# shutdown_circuit.net
KiCad netlist of a schematic drawn in Altium Designer
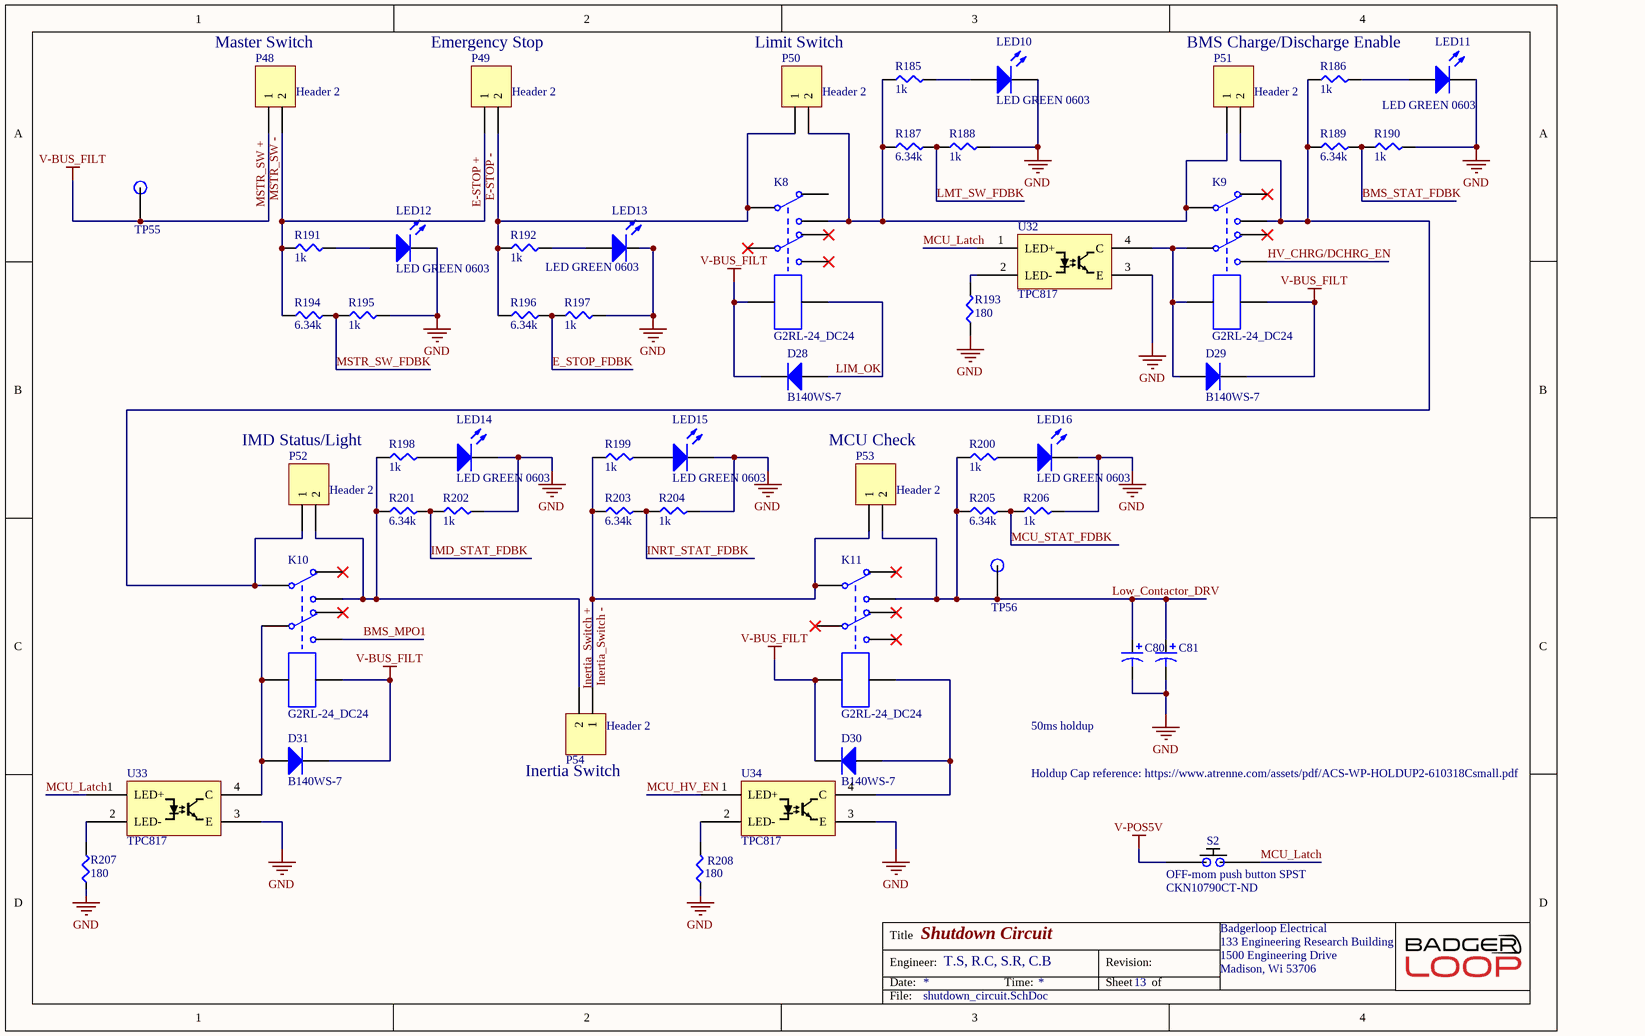
[diagram p0: shutdown_circuit.SchDoc]

(export (version "E")
  (design (tool "Eeschema 10.0.6"))
  (components
    (comp (ref "C80")
      (value "PCR1J101MCL1GS")
      (footprint "CAPAE110103X126M")
      (description "CAP ALUM POLY 100UF 20% 63V SMD")
      (fields (field (name "MANUFACTURER") "Nichicon") (field (name "TOLERANCE") "20%"))
      (libsource (lib "capacitors") (part "PCR1J101MCL1GS"))
    )
    (comp (ref "C81")
      (value "PCR1J101MCL1GS")
      (footprint "CAPAE110103X126M")
      (description "CAP ALUM POLY 100UF 20% 63V SMD")
      (fields (field (name "MANUFACTURER") "Nichicon") (field (name "TOLERANCE") "20%"))
      (libsource (lib "capacitors") (part "PCR1J101MCL1GS"))
    )
    (comp (ref "D28")
      (value "B140WS-7")
      (footprint "SODFL250X110-2N")
      (description "Diode Schottky 40V 1A 2-Pin SOD-323 T/R")
      (fields (field (name "MANUFACTURER") "Diodes"))
      (libsource (lib "misc") (part "B140WS-7"))
    )
    (comp (ref "D29")
      (value "B140WS-7")
      (footprint "SODFL250X110-2N")
      (description "Diode Schottky 40V 1A 2-Pin SOD-323 T/R")
      (fields (field (name "MANUFACTURER") "Diodes"))
      (libsource (lib "misc") (part "B140WS-7"))
    )
    (comp (ref "D30")
      (value "B140WS-7")
      (footprint "SODFL250X110-2N")
      (description "Diode Schottky 40V 1A 2-Pin SOD-323 T/R")
      (fields (field (name "MANUFACTURER") "Diodes"))
      (libsource (lib "misc") (part "B140WS-7"))
    )
    (comp (ref "D31")
      (value "B140WS-7")
      (footprint "SODFL250X110-2N")
      (description "Diode Schottky 40V 1A 2-Pin SOD-323 T/R")
      (fields (field (name "MANUFACTURER") "Diodes"))
      (libsource (lib "misc") (part "B140WS-7"))
    )
    (comp (ref "K8")
      (value "G2RL-24_DC24")
      (footprint "G2RL")
      (description "RELAY GEN PURPOSE DPDT 8A 24V")
      (fields (field (name "MANUFACTURER") "Omron") (field (name "MANUFACTURER PART NUMBER") "G2RL-24-DC24"))
      (libsource (lib "misc") (part "G2RL-24_DC24"))
    )
    (comp (ref "K9")
      (value "G2RL-24_DC24")
      (footprint "G2RL")
      (description "RELAY GEN PURPOSE DPDT 8A 24V")
      (fields (field (name "MANUFACTURER") "Omron") (field (name "MANUFACTURER PART NUMBER") "G2RL-24-DC24"))
      (libsource (lib "misc") (part "G2RL-24_DC24"))
    )
    (comp (ref "K10")
      (value "G2RL-24_DC24")
      (footprint "G2RL")
      (description "RELAY GEN PURPOSE DPDT 8A 24V")
      (fields (field (name "MANUFACTURER") "Omron") (field (name "MANUFACTURER PART NUMBER") "G2RL-24-DC24"))
      (libsource (lib "misc") (part "G2RL-24_DC24"))
    )
    (comp (ref "K11")
      (value "G2RL-24_DC24")
      (footprint "G2RL")
      (description "RELAY GEN PURPOSE DPDT 8A 24V")
      (fields (field (name "MANUFACTURER") "Omron") (field (name "MANUFACTURER PART NUMBER") "G2RL-24-DC24"))
      (libsource (lib "misc") (part "G2RL-24_DC24"))
    )
    (comp (ref "LED10")
      (value "LED GREEN 0603")
      (footprint "LED 0603 GREEN")
      (fields (field (name "MANUFACTURER") "Lite-On Inc."))
      (libsource (lib "misc") (part "LED GREEN 0603"))
    )
    (comp (ref "LED11")
      (value "LED GREEN 0603")
      (footprint "LED 0603 GREEN")
      (fields (field (name "MANUFACTURER") "Lite-On Inc."))
      (libsource (lib "misc") (part "LED GREEN 0603"))
    )
    (comp (ref "LED12")
      (value "LED GREEN 0603")
      (footprint "LED 0603 GREEN")
      (fields (field (name "MANUFACTURER") "Lite-On Inc."))
      (libsource (lib "misc") (part "LED GREEN 0603"))
    )
    (comp (ref "LED13")
      (value "LED GREEN 0603")
      (footprint "LED 0603 GREEN")
      (fields (field (name "MANUFACTURER") "Lite-On Inc."))
      (libsource (lib "misc") (part "LED GREEN 0603"))
    )
    (comp (ref "LED14")
      (value "LED GREEN 0603")
      (footprint "LED 0603 GREEN")
      (fields (field (name "MANUFACTURER") "Lite-On Inc."))
      (libsource (lib "misc") (part "LED GREEN 0603"))
    )
    (comp (ref "LED15")
      (value "LED GREEN 0603")
      (footprint "LED 0603 GREEN")
      (fields (field (name "MANUFACTURER") "Lite-On Inc."))
      (libsource (lib "misc") (part "LED GREEN 0603"))
    )
    (comp (ref "LED16")
      (value "LED GREEN 0603")
      (footprint "LED 0603 GREEN")
      (fields (field (name "MANUFACTURER") "Lite-On Inc."))
      (libsource (lib "misc") (part "LED GREEN 0603"))
    )
    (comp (ref "P48")
      (value "Header 2")
      (footprint "Pin Header 1x2 TH Pitch 2.54mm")
      (description "Header, 2-Pin")
      (fields (field (name "PUBLISHER") "Altium Limited"))
      (libsource (lib "") (part "Header 2_1"))
    )
    (comp (ref "P49")
      (value "Header 2")
      (footprint "Pin Header 1x2 TH Pitch 2.54mm")
      (description "Header, 2-Pin")
      (fields (field (name "PUBLISHER") "Altium Limited"))
      (libsource (lib "") (part "Header 2_1"))
    )
    (comp (ref "P50")
      (value "Header 2")
      (footprint "Pin Header 1x2 TH Pitch 2.54mm")
      (description "Header, 2-Pin")
      (fields (field (name "PUBLISHER") "Altium Limited"))
      (libsource (lib "") (part "Header 2_1"))
    )
    (comp (ref "P51")
      (value "Header 2")
      (footprint "Pin Header 1x2 TH Pitch 2.54mm")
      (description "Header, 2-Pin")
      (fields (field (name "PUBLISHER") "Altium Limited"))
      (libsource (lib "") (part "Header 2_1"))
    )
    (comp (ref "P52")
      (value "Header 2")
      (footprint "Pin Header 1x2 TH Pitch 2.54mm")
      (description "Header, 2-Pin")
      (fields (field (name "PUBLISHER") "Altium Limited"))
      (libsource (lib "") (part "Header 2_1"))
    )
    (comp (ref "P53")
      (value "Header 2")
      (footprint "Pin Header 1x2 TH Pitch 2.54mm")
      (description "Header, 2-Pin")
      (fields (field (name "PUBLISHER") "Altium Limited"))
      (libsource (lib "") (part "Header 2_1"))
    )
    (comp (ref "P54")
      (value "Header 2")
      (footprint "Pin Header 1x2 TH Pitch 2.54mm")
      (description "Header, 2-Pin")
      (fields (field (name "PUBLISHER") "Altium Limited"))
      (libsource (lib "connector") (part "Header 2"))
    )
    (comp (ref "R185")
      (value "1k")
      (footprint "SMD-0805-RES")
      (description "RES SMD 1K OHM 1% 1/2W 0805")
      (fields
        (field (name "PART NUMBER") "ERJ-P06F1001V")
        (field (name "DIGI-KEY PART NUMBER") "P16058CT-ND")
      )
      (libsource (lib "resistors") (part "ERJ-P06F1001V"))
    )
    (comp (ref "R186")
      (value "1k")
      (footprint "SMD-0805-RES")
      (description "RES SMD 1K OHM 1% 1/2W 0805")
      (fields
        (field (name "PART NUMBER") "ERJ-P06F1001V")
        (field (name "DIGI-KEY PART NUMBER") "P16058CT-ND")
      )
      (libsource (lib "resistors") (part "ERJ-P06F1001V"))
    )
    (comp (ref "R187")
      (value "6.34k")
      (footprint "SMD-0805-RES")
      (description "RES SMD 6.34K OHM 1% 1/8W 0805")
      (fields
        (field (name "PART NUMBER") "ERJ-6ENF6341V")
        (field (name "DIGI-KEY PART NUMBER") "P6.34KCCT-ND")
      )
      (libsource (lib "resistors") (part "ERJ-6ENF6341V"))
    )
    (comp (ref "R188")
      (value "1k")
      (footprint "SMD-0805-RES")
      (description "RES SMD 1K OHM 1% 1/2W 0805")
      (fields
        (field (name "PART NUMBER") "ERJ-P06F1001V")
        (field (name "DIGI-KEY PART NUMBER") "P16058CT-ND")
      )
      (libsource (lib "resistors") (part "ERJ-P06F1001V"))
    )
    (comp (ref "R189")
      (value "6.34k")
      (footprint "SMD-0805-RES")
      (description "RES SMD 6.34K OHM 1% 1/8W 0805")
      (fields
        (field (name "PART NUMBER") "ERJ-6ENF6341V")
        (field (name "DIGI-KEY PART NUMBER") "P6.34KCCT-ND")
      )
      (libsource (lib "resistors") (part "ERJ-6ENF6341V"))
    )
    (comp (ref "R190")
      (value "1k")
      (footprint "SMD-0805-RES")
      (description "RES SMD 1K OHM 1% 1/2W 0805")
      (fields
        (field (name "PART NUMBER") "ERJ-P06F1001V")
        (field (name "DIGI-KEY PART NUMBER") "P16058CT-ND")
      )
      (libsource (lib "resistors") (part "ERJ-P06F1001V"))
    )
    (comp (ref "R191")
      (value "1k")
      (footprint "SMD-0805-RES")
      (description "RES SMD 1K OHM 1% 1/2W 0805")
      (fields
        (field (name "PART NUMBER") "ERJ-P06F1001V")
        (field (name "DIGI-KEY PART NUMBER") "P16058CT-ND")
      )
      (libsource (lib "resistors") (part "ERJ-P06F1001V"))
    )
    (comp (ref "R192")
      (value "1k")
      (footprint "SMD-0805-RES")
      (description "RES SMD 1K OHM 1% 1/2W 0805")
      (fields
        (field (name "PART NUMBER") "ERJ-P06F1001V")
        (field (name "DIGI-KEY PART NUMBER") "P16058CT-ND")
      )
      (libsource (lib "resistors") (part "ERJ-P06F1001V"))
    )
    (comp (ref "R193")
      (value "180")
      (footprint "SMD-0805-RES")
      (description "RES SMD 180 OHM 1% 1/8W 0805")
      (fields (field (name "PART NUMBER") "ERJ-6ENF1800V") (field (name "DIGI-KEY PART NUMBER") "P180CCT-ND"))
      (libsource (lib "resistors") (part "ERJ-6ENF1800V"))
    )
    (comp (ref "R194")
      (value "6.34k")
      (footprint "SMD-0805-RES")
      (description "RES SMD 6.34K OHM 1% 1/8W 0805")
      (fields
        (field (name "PART NUMBER") "ERJ-6ENF6341V")
        (field (name "DIGI-KEY PART NUMBER") "P6.34KCCT-ND")
      )
      (libsource (lib "resistors") (part "ERJ-6ENF6341V"))
    )
    (comp (ref "R195")
      (value "1k")
      (footprint "SMD-0805-RES")
      (description "RES SMD 1K OHM 1% 1/2W 0805")
      (fields
        (field (name "PART NUMBER") "ERJ-P06F1001V")
        (field (name "DIGI-KEY PART NUMBER") "P16058CT-ND")
      )
      (libsource (lib "resistors") (part "ERJ-P06F1001V"))
    )
    (comp (ref "R196")
      (value "6.34k")
      (footprint "SMD-0805-RES")
      (description "RES SMD 6.34K OHM 1% 1/8W 0805")
      (fields
        (field (name "PART NUMBER") "ERJ-6ENF6341V")
        (field (name "DIGI-KEY PART NUMBER") "P6.34KCCT-ND")
      )
      (libsource (lib "resistors") (part "ERJ-6ENF6341V"))
    )
    (comp (ref "R197")
      (value "1k")
      (footprint "SMD-0805-RES")
      (description "RES SMD 1K OHM 1% 1/2W 0805")
      (fields
        (field (name "PART NUMBER") "ERJ-P06F1001V")
        (field (name "DIGI-KEY PART NUMBER") "P16058CT-ND")
      )
      (libsource (lib "resistors") (part "ERJ-P06F1001V"))
    )
    (comp (ref "R198")
      (value "1k")
      (footprint "SMD-0805-RES")
      (description "RES SMD 1K OHM 1% 1/2W 0805")
      (fields
        (field (name "PART NUMBER") "ERJ-P06F1001V")
        (field (name "DIGI-KEY PART NUMBER") "P16058CT-ND")
      )
      (libsource (lib "resistors") (part "ERJ-P06F1001V"))
    )
    (comp (ref "R199")
      (value "1k")
      (footprint "SMD-0805-RES")
      (description "RES SMD 1K OHM 1% 1/2W 0805")
      (fields
        (field (name "PART NUMBER") "ERJ-P06F1001V")
        (field (name "DIGI-KEY PART NUMBER") "P16058CT-ND")
      )
      (libsource (lib "resistors") (part "ERJ-P06F1001V"))
    )
    (comp (ref "R200")
      (value "1k")
      (footprint "SMD-0805-RES")
      (description "RES SMD 1K OHM 1% 1/2W 0805")
      (fields
        (field (name "PART NUMBER") "ERJ-P06F1001V")
        (field (name "DIGI-KEY PART NUMBER") "P16058CT-ND")
      )
      (libsource (lib "resistors") (part "ERJ-P06F1001V"))
    )
    (comp (ref "R201")
      (value "6.34k")
      (footprint "SMD-0805-RES")
      (description "RES SMD 6.34K OHM 1% 1/8W 0805")
      (fields
        (field (name "PART NUMBER") "ERJ-6ENF6341V")
        (field (name "DIGI-KEY PART NUMBER") "P6.34KCCT-ND")
      )
      (libsource (lib "resistors") (part "ERJ-6ENF6341V"))
    )
    (comp (ref "R202")
      (value "1k")
      (footprint "SMD-0805-RES")
      (description "RES SMD 1K OHM 1% 1/2W 0805")
      (fields
        (field (name "PART NUMBER") "ERJ-P06F1001V")
        (field (name "DIGI-KEY PART NUMBER") "P16058CT-ND")
      )
      (libsource (lib "resistors") (part "ERJ-P06F1001V"))
    )
    (comp (ref "R203")
      (value "6.34k")
      (footprint "SMD-0805-RES")
      (description "RES SMD 6.34K OHM 1% 1/8W 0805")
      (fields
        (field (name "PART NUMBER") "ERJ-6ENF6341V")
        (field (name "DIGI-KEY PART NUMBER") "P6.34KCCT-ND")
      )
      (libsource (lib "resistors") (part "ERJ-6ENF6341V"))
    )
    (comp (ref "R204")
      (value "1k")
      (footprint "SMD-0805-RES")
      (description "RES SMD 1K OHM 1% 1/2W 0805")
      (fields
        (field (name "PART NUMBER") "ERJ-P06F1001V")
        (field (name "DIGI-KEY PART NUMBER") "P16058CT-ND")
      )
      (libsource (lib "resistors") (part "ERJ-P06F1001V"))
    )
    (comp (ref "R205")
      (value "6.34k")
      (footprint "SMD-0805-RES")
      (description "RES SMD 6.34K OHM 1% 1/8W 0805")
      (fields
        (field (name "PART NUMBER") "ERJ-6ENF6341V")
        (field (name "DIGI-KEY PART NUMBER") "P6.34KCCT-ND")
      )
      (libsource (lib "resistors") (part "ERJ-6ENF6341V"))
    )
    (comp (ref "R206")
      (value "1k")
      (footprint "SMD-0805-RES")
      (description "RES SMD 1K OHM 1% 1/2W 0805")
      (fields
        (field (name "PART NUMBER") "ERJ-P06F1001V")
        (field (name "DIGI-KEY PART NUMBER") "P16058CT-ND")
      )
      (libsource (lib "resistors") (part "ERJ-P06F1001V"))
    )
    (comp (ref "R207")
      (value "180")
      (footprint "SMD-0805-RES")
      (description "RES SMD 180 OHM 1% 1/8W 0805")
      (fields (field (name "PART NUMBER") "ERJ-6ENF1800V") (field (name "DIGI-KEY PART NUMBER") "P180CCT-ND"))
      (libsource (lib "resistors") (part "ERJ-6ENF1800V"))
    )
    (comp (ref "R208")
      (value "180")
      (footprint "SMD-0805-RES")
      (description "RES SMD 180 OHM 1% 1/8W 0805")
      (fields (field (name "PART NUMBER") "ERJ-6ENF1800V") (field (name "DIGI-KEY PART NUMBER") "P180CCT-ND"))
      (libsource (lib "resistors") (part "ERJ-6ENF1800V"))
    )
    (comp (ref "S2")
      (value "OFF-mom push button SPST")
      (footprint "K12SCS1.55NOLFTX")
      (description "OFF-mom push button SPST K12SCS1.55NOLFTX")
      (fields
        (field (name "MANUFACTURER") "ITT C&K")
        (field (name "MANUFACTURER PART NUMBER") "K12SCS1.55NOLFTX")
        (field (name "SUPPLIER PART NUMBER 1") "CKN10790CT-ND")
      )
      (libsource (lib "*") (part "K12SCS1.55NOLFTX"))
    )
    (comp (ref "TP55")
      (value "TP")
      (footprint "Test Point")
      (description "SMD TEST POINT")
      (libsource (lib "misc") (part "TP"))
    )
    (comp (ref "TP56")
      (value "TP")
      (footprint "Test Point")
      (description "SMD TEST POINT")
      (libsource (lib "misc") (part "TP"))
    )
    (comp (ref "U32")
      (value "TPC817")
      (footprint "SOT200P1005X328-5N")
      (description "OPTOISO 5KV TRANS 4SOP")
      (fields (field (name "MANUFACTURER") "Taiwan Semi"))
      (libsource (lib "ic") (part "TPC817"))
    )
    (comp (ref "U33")
      (value "TPC817")
      (footprint "SOT200P1005X328-5N")
      (description "OPTOISO 5KV TRANS 4SOP")
      (fields (field (name "MANUFACTURER") "Taiwan Semi"))
      (libsource (lib "ic") (part "TPC817"))
    )
    (comp (ref "U34")
      (value "TPC817")
      (footprint "SOT200P1005X328-5N")
      (description "OPTOISO 5KV TRANS 4SOP")
      (fields (field (name "MANUFACTURER") "Taiwan Semi"))
      (libsource (lib "ic") (part "TPC817"))
    )
  )
  (nets
    (net (code "1") (name "/BMS_MPO1") (class "Default")
      (node (ref "K10") (pin "5") (pinfunction "5_5") (pintype "passive"))
    )
    (net (code "2") (name "/BMS_STAT_FDBK") (class "Default")
      (node (ref "R189") (pin "2") (pinfunction "2_2") (pintype "passive"))
      (node (ref "R190") (pin "1") (pinfunction "1_1") (pintype "passive"))
    )
    (net (code "3") (name "/E-STOP +") (class "Default")
      (node (ref "P48") (pin "2") (pinfunction "2_2") (pintype "passive"))
      (node (ref "P49") (pin "1") (pinfunction "1_1") (pintype "passive"))
      (node (ref "R191") (pin "1") (pinfunction "1_1") (pintype "passive"))
      (node (ref "R194") (pin "1") (pinfunction "1_1") (pintype "passive"))
    )
    (net (code "4") (name "/E-STOP -") (class "Default")
      (node (ref "K8") (pin "3") (pinfunction "3_3") (pintype "passive"))
      (node (ref "P49") (pin "2") (pinfunction "2_2") (pintype "passive"))
      (node (ref "P50") (pin "1") (pinfunction "1_1") (pintype "passive"))
      (node (ref "R192") (pin "1") (pinfunction "1_1") (pintype "passive"))
      (node (ref "R196") (pin "1") (pinfunction "1_1") (pintype "passive"))
    )
    (net (code "5") (name "/E_STOP_FDBK") (class "Default")
      (node (ref "R196") (pin "2") (pinfunction "2_2") (pintype "passive"))
      (node (ref "R197") (pin "1") (pinfunction "1_1") (pintype "passive"))
    )
    (net (code "6") (name "/HV_CHRG{slash}DCHRG_EN") (class "Default")
      (node (ref "K9") (pin "5") (pinfunction "5_5") (pintype "passive"))
    )
    (net (code "7") (name "/IMD_STAT_FDBK") (class "Default")
      (node (ref "R201") (pin "2") (pinfunction "2_2") (pintype "passive"))
      (node (ref "R202") (pin "1") (pinfunction "1_1") (pintype "passive"))
    )
    (net (code "8") (name "/INRT_STAT_FDBK") (class "Default")
      (node (ref "R203") (pin "2") (pinfunction "2_2") (pintype "passive"))
      (node (ref "R204") (pin "1") (pinfunction "1_1") (pintype "passive"))
    )
    (net (code "9") (name "/Inertia_Switch +") (class "Default")
      (node (ref "K10") (pin "4") (pinfunction "4_4") (pintype "passive"))
      (node (ref "P52") (pin "2") (pinfunction "2_2") (pintype "passive"))
      (node (ref "P54") (pin "2") (pinfunction "2_2") (pintype "passive"))
      (node (ref "R198") (pin "1") (pinfunction "1_1") (pintype "passive"))
      (node (ref "R201") (pin "1") (pinfunction "1_1") (pintype "passive"))
    )
    (net (code "10") (name "/Inertia_Switch -") (class "Default")
      (node (ref "K11") (pin "3") (pinfunction "3_3") (pintype "passive"))
      (node (ref "P53") (pin "1") (pinfunction "1_1") (pintype "passive"))
      (node (ref "P54") (pin "1") (pinfunction "1_1") (pintype "passive"))
      (node (ref "R199") (pin "1") (pinfunction "1_1") (pintype "passive"))
      (node (ref "R203") (pin "1") (pinfunction "1_1") (pintype "passive"))
    )
    (net (code "11") (name "/LIM_OK") (class "Default")
      (node (ref "D28") (pin "1") (pinfunction "A_1") (pintype "passive"))
      (node (ref "K8") (pin "8") (pinfunction "8_8") (pintype "passive"))
    )
    (net (code "12") (name "/LMT_SW_FDBK") (class "Default")
      (node (ref "R187") (pin "2") (pinfunction "2_2") (pintype "passive"))
      (node (ref "R188") (pin "1") (pinfunction "1_1") (pintype "passive"))
    )
    (net (code "13") (name "/Low_Contactor_DRV") (class "Default")
      (node (ref "C80") (pin "1") (pinfunction "1_1") (pintype "passive"))
      (node (ref "C81") (pin "1") (pinfunction "1_1") (pintype "passive"))
      (node (ref "K11") (pin "4") (pinfunction "4_4") (pintype "passive"))
      (node (ref "P53") (pin "2") (pinfunction "2_2") (pintype "passive"))
      (node (ref "R200") (pin "1") (pinfunction "1_1") (pintype "passive"))
      (node (ref "R205") (pin "1") (pinfunction "1_1") (pintype "passive"))
      (node (ref "TP56") (pin "1") (pinfunction "1_1") (pintype "passive"))
    )
    (net (code "14") (name "/MCU_HV_EN") (class "Default")
      (node (ref "U34") (pin "1") (pinfunction "LED+_1") (pintype "passive"))
    )
    (net (code "15") (name "/MCU_Latch") (class "Default")
      (node (ref "S2") (pin "2") (pinfunction "2_2") (pintype "passive"))
      (node (ref "U32") (pin "1") (pinfunction "LED+_1") (pintype "passive"))
      (node (ref "U33") (pin "1") (pinfunction "LED+_1") (pintype "passive"))
    )
    (net (code "16") (name "/MCU_STAT_FDBK") (class "Default")
      (node (ref "R205") (pin "2") (pinfunction "2_2") (pintype "passive"))
      (node (ref "R206") (pin "1") (pinfunction "1_1") (pintype "passive"))
    )
    (net (code "17") (name "/MSTR_SW_FDBK") (class "Default")
      (node (ref "R194") (pin "2") (pinfunction "2_2") (pintype "passive"))
      (node (ref "R195") (pin "1") (pinfunction "1_1") (pintype "passive"))
    )
    (net (code "18") (name "GND") (class "Default")
      (node (ref "C80") (pin "2") (pinfunction "2_2") (pintype "passive"))
      (node (ref "C81") (pin "2") (pinfunction "2_2") (pintype "passive"))
      (node (ref "LED10") (pin "2") (pinfunction "K_2") (pintype "passive"))
      (node (ref "LED11") (pin "2") (pinfunction "K_2") (pintype "passive"))
      (node (ref "LED12") (pin "2") (pinfunction "K_2") (pintype "passive"))
      (node (ref "LED13") (pin "2") (pinfunction "K_2") (pintype "passive"))
      (node (ref "LED14") (pin "2") (pinfunction "K_2") (pintype "passive"))
      (node (ref "LED15") (pin "2") (pinfunction "K_2") (pintype "passive"))
      (node (ref "LED16") (pin "2") (pinfunction "K_2") (pintype "passive"))
      (node (ref "R188") (pin "2") (pinfunction "2_2") (pintype "passive"))
      (node (ref "R190") (pin "2") (pinfunction "2_2") (pintype "passive"))
      (node (ref "R193") (pin "1") (pinfunction "1_1") (pintype "passive"))
      (node (ref "R195") (pin "2") (pinfunction "2_2") (pintype "passive"))
      (node (ref "R197") (pin "2") (pinfunction "2_2") (pintype "passive"))
      (node (ref "R202") (pin "2") (pinfunction "2_2") (pintype "passive"))
      (node (ref "R204") (pin "2") (pinfunction "2_2") (pintype "passive"))
      (node (ref "R206") (pin "2") (pinfunction "2_2") (pintype "passive"))
      (node (ref "R207") (pin "1") (pinfunction "1_1") (pintype "passive"))
      (node (ref "R208") (pin "1") (pinfunction "1_1") (pintype "passive"))
      (node (ref "U32") (pin "3") (pinfunction "E_3") (pintype "passive"))
      (node (ref "U33") (pin "3") (pinfunction "E_3") (pintype "passive"))
      (node (ref "U34") (pin "3") (pinfunction "E_3") (pintype "passive"))
    )
    (net (code "19") (name "Net-(D29-A)") (class "Default")
      (node (ref "D29") (pin "1") (pinfunction "A_1") (pintype "passive"))
      (node (ref "K9") (pin "1") (pinfunction "1_1") (pintype "passive"))
      (node (ref "K9") (pin "6") (pinfunction "6_6") (pintype "passive"))
      (node (ref "U32") (pin "4") (pinfunction "C_4") (pintype "passive"))
    )
    (net (code "20") (name "Net-(D30-A)") (class "Default")
      (node (ref "D30") (pin "1") (pinfunction "A_1") (pintype "passive"))
      (node (ref "K11") (pin "8") (pinfunction "8_8") (pintype "passive"))
      (node (ref "U34") (pin "4") (pinfunction "C_4") (pintype "passive"))
    )
    (net (code "21") (name "Net-(D31-A)") (class "Default")
      (node (ref "D31") (pin "1") (pinfunction "A_1") (pintype "passive"))
      (node (ref "K10") (pin "1") (pinfunction "1_1") (pintype "passive"))
      (node (ref "K10") (pin "6") (pinfunction "6_6") (pintype "passive"))
      (node (ref "U33") (pin "4") (pinfunction "C_4") (pintype "passive"))
    )
    (net (code "22") (name "Net-(K8-Pad4)") (class "Default")
      (node (ref "K8") (pin "4") (pinfunction "4_4") (pintype "passive"))
      (node (ref "K9") (pin "3") (pinfunction "3_3") (pintype "passive"))
      (node (ref "P50") (pin "2") (pinfunction "2_2") (pintype "passive"))
      (node (ref "P51") (pin "1") (pinfunction "1_1") (pintype "passive"))
      (node (ref "R185") (pin "1") (pinfunction "1_1") (pintype "passive"))
      (node (ref "R187") (pin "1") (pinfunction "1_1") (pintype "passive"))
    )
    (net (code "23") (name "Net-(K10-Pad3)") (class "Default")
      (node (ref "K10") (pin "3") (pinfunction "3_3") (pintype "passive"))
      (node (ref "K9") (pin "4") (pinfunction "4_4") (pintype "passive"))
      (node (ref "P51") (pin "2") (pinfunction "2_2") (pintype "passive"))
      (node (ref "P52") (pin "1") (pinfunction "1_1") (pintype "passive"))
      (node (ref "R186") (pin "1") (pinfunction "1_1") (pintype "passive"))
      (node (ref "R189") (pin "1") (pinfunction "1_1") (pintype "passive"))
    )
    (net (code "24") (name "Net-(LED10-A)") (class "Default")
      (node (ref "LED10") (pin "1") (pinfunction "A_1") (pintype "passive"))
      (node (ref "R185") (pin "2") (pinfunction "2_2") (pintype "passive"))
    )
    (net (code "25") (name "Net-(LED11-A)") (class "Default")
      (node (ref "LED11") (pin "1") (pinfunction "A_1") (pintype "passive"))
      (node (ref "R186") (pin "2") (pinfunction "2_2") (pintype "passive"))
    )
    (net (code "26") (name "Net-(LED12-A)") (class "Default")
      (node (ref "LED12") (pin "1") (pinfunction "A_1") (pintype "passive"))
      (node (ref "R191") (pin "2") (pinfunction "2_2") (pintype "passive"))
    )
    (net (code "27") (name "Net-(LED13-A)") (class "Default")
      (node (ref "LED13") (pin "1") (pinfunction "A_1") (pintype "passive"))
      (node (ref "R192") (pin "2") (pinfunction "2_2") (pintype "passive"))
    )
    (net (code "28") (name "Net-(LED14-A)") (class "Default")
      (node (ref "LED14") (pin "1") (pinfunction "A_1") (pintype "passive"))
      (node (ref "R198") (pin "2") (pinfunction "2_2") (pintype "passive"))
    )
    (net (code "29") (name "Net-(LED15-A)") (class "Default")
      (node (ref "LED15") (pin "1") (pinfunction "A_1") (pintype "passive"))
      (node (ref "R199") (pin "2") (pinfunction "2_2") (pintype "passive"))
    )
    (net (code "30") (name "Net-(LED16-A)") (class "Default")
      (node (ref "LED16") (pin "1") (pinfunction "A_1") (pintype "passive"))
      (node (ref "R200") (pin "2") (pinfunction "2_2") (pintype "passive"))
    )
    (net (code "31") (name "Net-(U32-LED-)") (class "Default")
      (node (ref "R193") (pin "2") (pinfunction "2_2") (pintype "passive"))
      (node (ref "U32") (pin "2") (pinfunction "LED-_2") (pintype "passive"))
    )
    (net (code "32") (name "Net-(U33-LED-)") (class "Default")
      (node (ref "R207") (pin "2") (pinfunction "2_2") (pintype "passive"))
      (node (ref "U33") (pin "2") (pinfunction "LED-_2") (pintype "passive"))
    )
    (net (code "33") (name "Net-(U34-LED-)") (class "Default")
      (node (ref "R208") (pin "2") (pinfunction "2_2") (pintype "passive"))
      (node (ref "U34") (pin "2") (pinfunction "LED-_2") (pintype "passive"))
    )
    (net (code "34") (name "V-BUS_FILT") (class "Default")
      (node (ref "D28") (pin "2") (pinfunction "K_2") (pintype "passive"))
      (node (ref "D29") (pin "2") (pinfunction "K_2") (pintype "passive"))
      (node (ref "D30") (pin "2") (pinfunction "K_2") (pintype "passive"))
      (node (ref "D31") (pin "2") (pinfunction "K_2") (pintype "passive"))
      (node (ref "K10") (pin "8") (pinfunction "8_8") (pintype "passive"))
      (node (ref "K11") (pin "1") (pinfunction "1_1") (pintype "passive"))
      (node (ref "K8") (pin "1") (pinfunction "1_1") (pintype "passive"))
      (node (ref "K9") (pin "8") (pinfunction "8_8") (pintype "passive"))
      (node (ref "P48") (pin "1") (pinfunction "1_1") (pintype "passive"))
      (node (ref "TP55") (pin "1") (pinfunction "1_1") (pintype "passive"))
    )
    (net (code "35") (name "V-POS5V") (class "Default")
      (node (ref "S2") (pin "1") (pinfunction "1_1") (pintype "passive"))
    )
    (net (code "36") (name "unconnected-(K8-Pad2)") (class "Default")
      (node (ref "K8") (pin "2") (pinfunction "2_2") (pintype "passive"))
    )
    (net (code "37") (name "unconnected-(K8-Pad5)") (class "Default")
      (node (ref "K8") (pin "5") (pinfunction "5_5") (pintype "passive+no_connect"))
    )
    (net (code "38") (name "unconnected-(K8-Pad6)") (class "Default")
      (node (ref "K8") (pin "6") (pinfunction "6_6") (pintype "passive+no_connect"))
    )
    (net (code "39") (name "unconnected-(K8-Pad7)") (class "Default")
      (node (ref "K8") (pin "7") (pinfunction "7_7") (pintype "passive+no_connect"))
    )
    (net (code "40") (name "unconnected-(K9-Pad2)") (class "Default")
      (node (ref "K9") (pin "2") (pinfunction "2_2") (pintype "passive+no_connect"))
    )
    (net (code "41") (name "unconnected-(K9-Pad7)") (class "Default")
      (node (ref "K9") (pin "7") (pinfunction "7_7") (pintype "passive+no_connect"))
    )
    (net (code "42") (name "unconnected-(K10-Pad2)") (class "Default")
      (node (ref "K10") (pin "2") (pinfunction "2_2") (pintype "passive+no_connect"))
    )
    (net (code "43") (name "unconnected-(K10-Pad7)") (class "Default")
      (node (ref "K10") (pin "7") (pinfunction "7_7") (pintype "passive+no_connect"))
    )
    (net (code "44") (name "unconnected-(K11-Pad2)") (class "Default")
      (node (ref "K11") (pin "2") (pinfunction "2_2") (pintype "passive+no_connect"))
    )
    (net (code "45") (name "unconnected-(K11-Pad5)") (class "Default")
      (node (ref "K11") (pin "5") (pinfunction "5_5") (pintype "passive+no_connect"))
    )
    (net (code "46") (name "unconnected-(K11-Pad6)") (class "Default")
      (node (ref "K11") (pin "6") (pinfunction "6_6") (pintype "passive+no_connect"))
    )
    (net (code "47") (name "unconnected-(K11-Pad7)") (class "Default")
      (node (ref "K11") (pin "7") (pinfunction "7_7") (pintype "passive+no_connect"))
    )
  )
)
